# PCB_3U_RJ45.net
KiCad netlist of a schematic drawn in Altium Designer
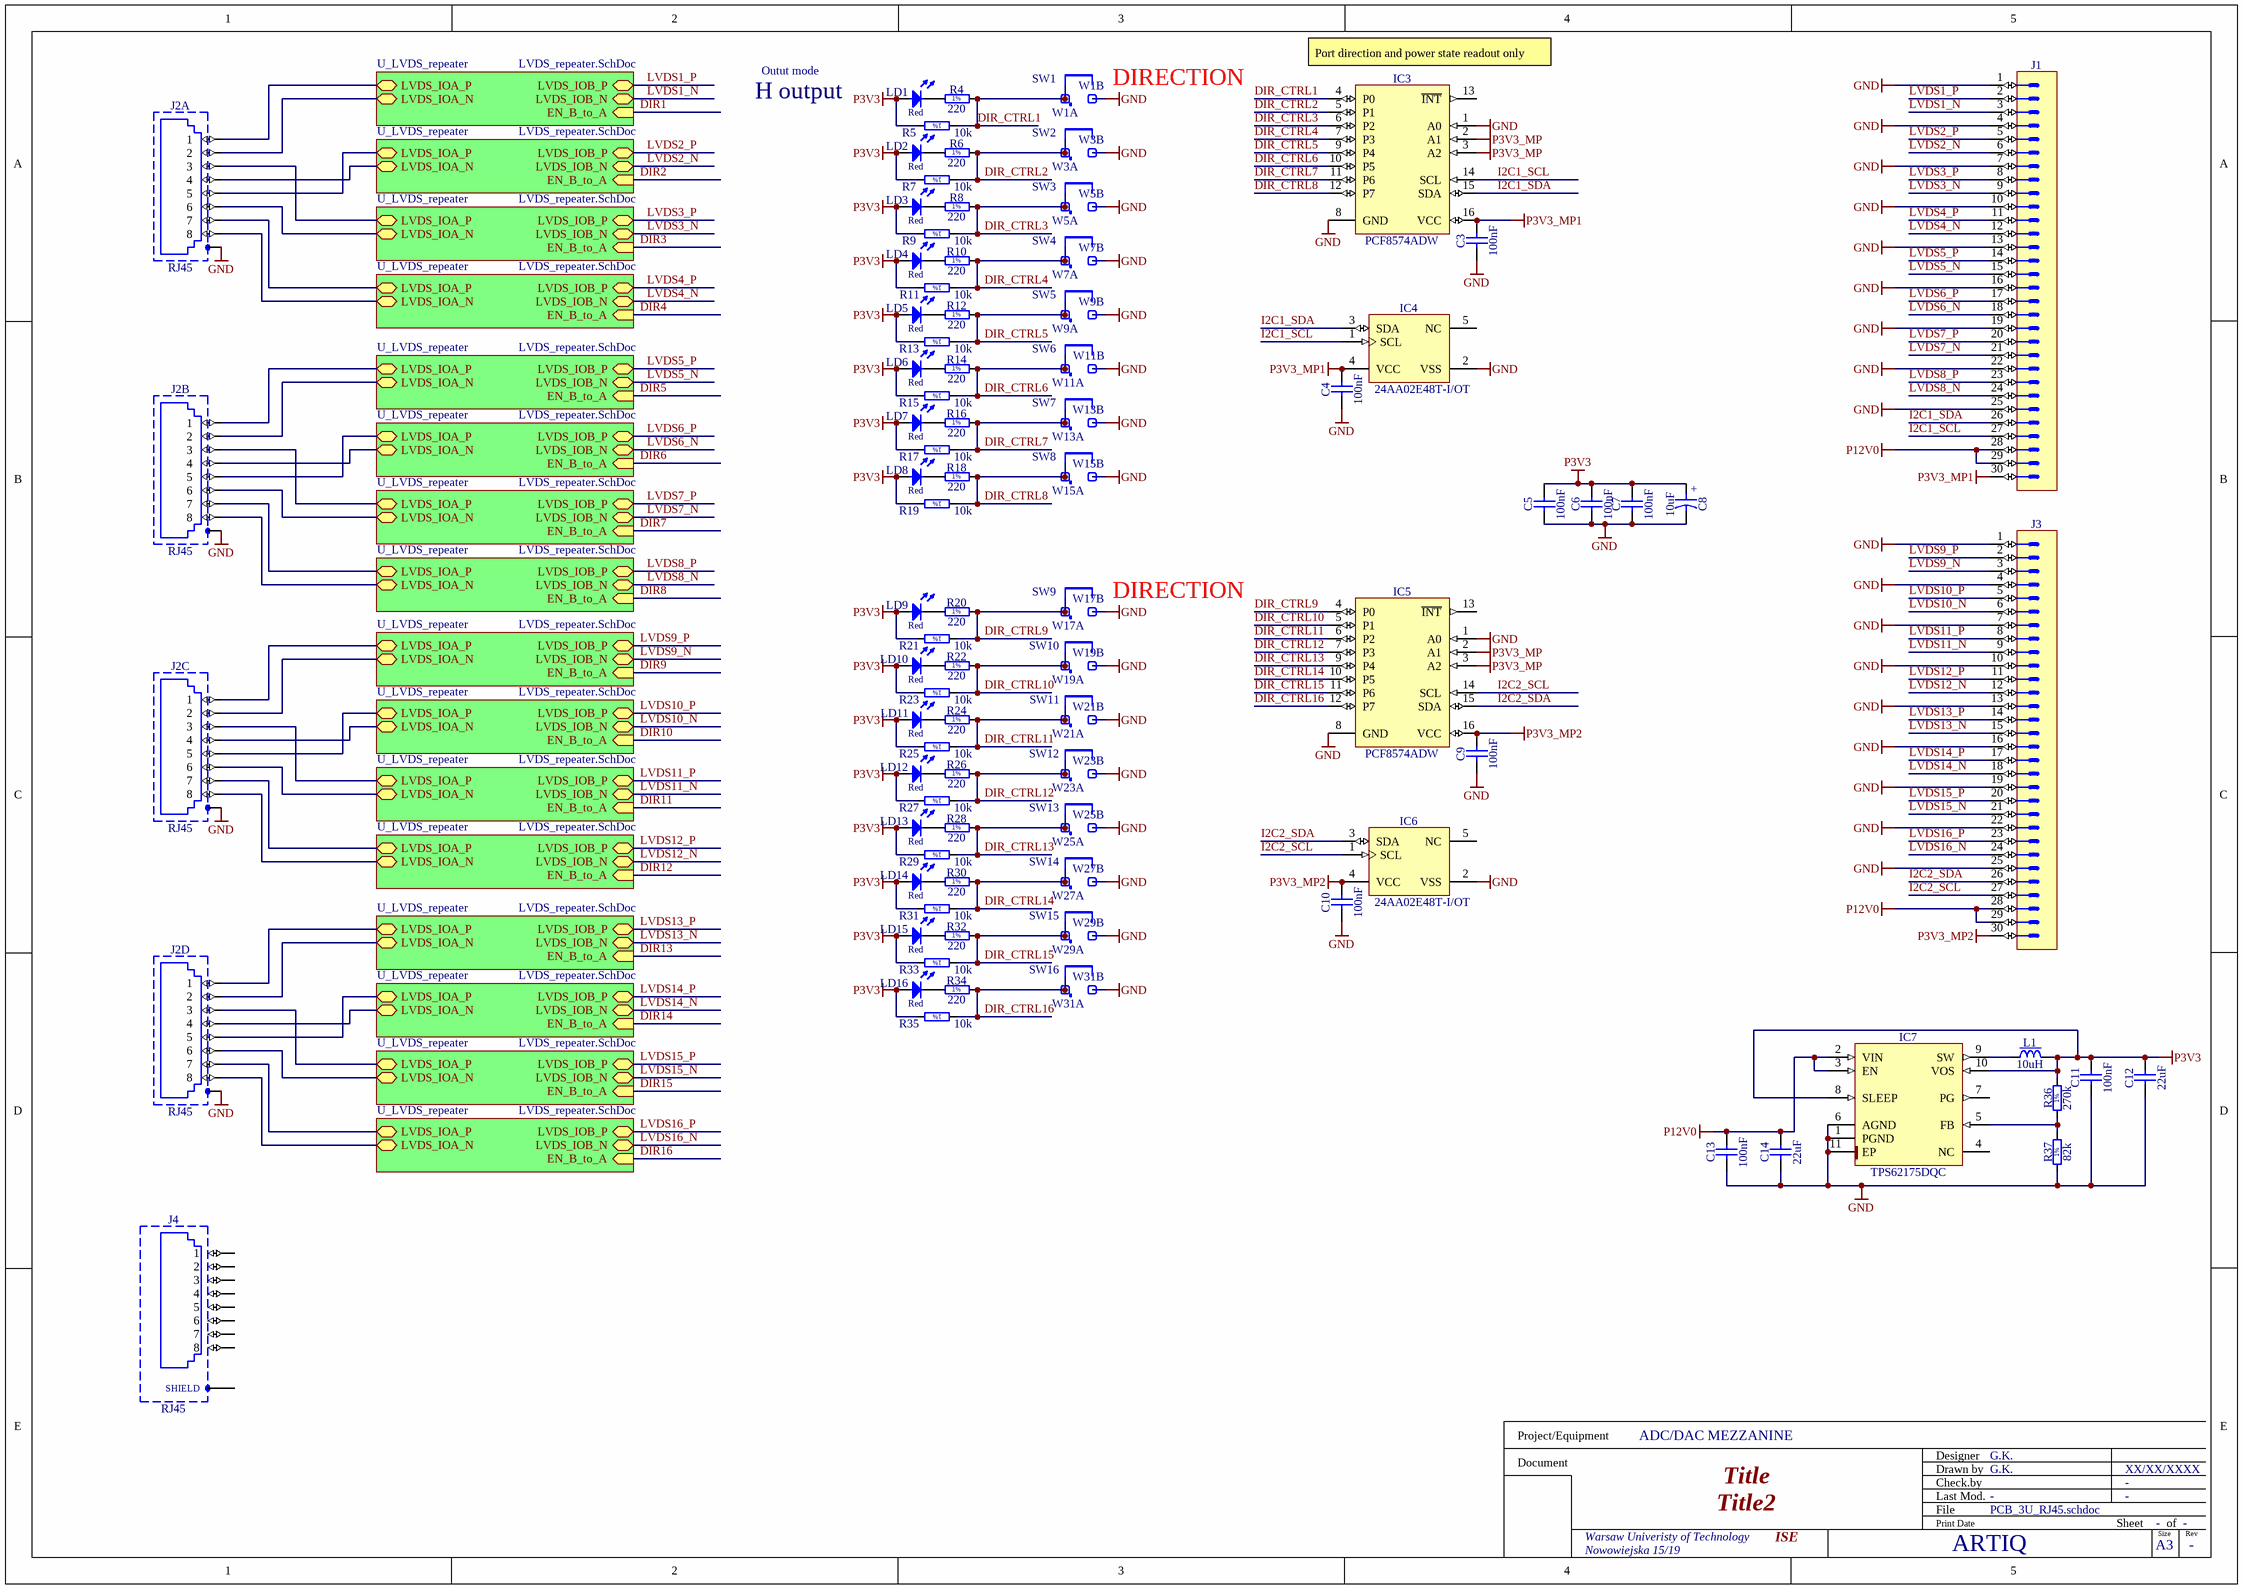
[diagram p0: PCB_3U_RJ45.schdoc]

(export (version "E")
  (design (tool "Eeschema 10.0.6"))
  (components
    (comp (ref "C3")
      (value "100nF")
      (footprint "CAPC1005X55N")
      (description "Non-polarised capacitor")
      (fields
        (field (name "PART NUMBER") "CC0402_100NF_16V_10%_X5R")
        (field (name "VOLTAGE") "16V")
        (field (name "AUTHOR") "CERN DEM JLC")
      )
      (libsource (lib "Capacitors") (part "Capacitor - non polarized"))
    )
    (comp (ref "C4")
      (value "100nF")
      (footprint "CAPC1005X55N")
      (description "Non-polarised capacitor")
      (fields
        (field (name "PART NUMBER") "CC0402_100NF_16V_10%_X5R")
        (field (name "VOLTAGE") "16V")
        (field (name "AUTHOR") "CERN DEM JLC")
      )
      (libsource (lib "Capacitors") (part "Capacitor - non polarized"))
    )
    (comp (ref "C5")
      (value "100nF")
      (footprint "CAPC1005X55N")
      (description "Non-polarised capacitor")
      (fields
        (field (name "PART NUMBER") "CC0402_100NF_16V_10%_X5R")
        (field (name "VOLTAGE") "16V")
        (field (name "AUTHOR") "CERN DEM JLC")
      )
      (libsource (lib "Capacitors") (part "Capacitor - non polarized"))
    )
    (comp (ref "C6")
      (value "100nF")
      (footprint "CAPC1005X55N")
      (description "Non-polarised capacitor")
      (fields
        (field (name "PART NUMBER") "CC0402_100NF_16V_10%_X5R")
        (field (name "VOLTAGE") "16V")
        (field (name "AUTHOR") "CERN DEM JLC")
      )
      (libsource (lib "Capacitors") (part "Capacitor - non polarized"))
    )
    (comp (ref "C7")
      (value "100nF")
      (footprint "CAPC1005X55N")
      (description "Non-polarised capacitor")
      (fields
        (field (name "PART NUMBER") "CC0402_100NF_16V_10%_X5R")
        (field (name "VOLTAGE") "16V")
        (field (name "AUTHOR") "CERN DEM JLC")
      )
      (libsource (lib "Capacitors") (part "Capacitor - non polarized"))
    )
    (comp (ref "C8")
      (value "10uF")
      (footprint "CAPAE430X540N")
      (description "Polarised capacitor")
      (fields
        (field (name "PART NUMBER") "CAE430-540_10UF_16V_20%")
        (field (name "VOLTAGE") "16V")
        (field (name "AUTHOR") "CERN DEM JLC")
      )
      (libsource (lib "Capacitors") (part "Capacitor - polarized"))
    )
    (comp (ref "C9")
      (value "100nF")
      (footprint "CAPC1005X55N")
      (description "Non-polarised capacitor")
      (fields
        (field (name "PART NUMBER") "CC0402_100NF_16V_10%_X5R")
        (field (name "VOLTAGE") "16V")
        (field (name "AUTHOR") "CERN DEM JLC")
      )
      (libsource (lib "Capacitors") (part "Capacitor - non polarized"))
    )
    (comp (ref "C10")
      (value "100nF")
      (footprint "CAPC1005X55N")
      (description "Non-polarised capacitor")
      (fields
        (field (name "PART NUMBER") "CC0402_100NF_16V_10%_X5R")
        (field (name "VOLTAGE") "16V")
        (field (name "AUTHOR") "CERN DEM JLC")
      )
      (libsource (lib "Capacitors") (part "Capacitor - non polarized"))
    )
    (comp (ref "C11")
      (value "100nF")
      (footprint "CAPC1005X55N")
      (description "Non-polarised capacitor")
      (fields
        (field (name "PART NUMBER") "CC0402_100NF_16V_10%_X5R")
        (field (name "VOLTAGE") "16V")
        (field (name "AUTHOR") "CERN DEM JLC")
      )
      (libsource (lib "Capacitors") (part "Capacitor - non polarized"))
    )
    (comp (ref "C12")
      (value "22uF")
      (footprint "CAPC2012X135N")
      (description "Non-polarised capacitor")
      (fields
        (field (name "PART NUMBER") "CC0805_22UF_16V_10%_X5R")
        (field (name "VOLTAGE") "16V")
        (field (name "AUTHOR") "CERN DEM JLC")
      )
      (libsource (lib "Capacitors") (part "Capacitor - non polarized"))
    )
    (comp (ref "C13")
      (value "100nF")
      (footprint "CAPC1005X55N")
      (description "Non-polarised capacitor")
      (fields
        (field (name "PART NUMBER") "CC0402_100NF_16V_10%_X5R")
        (field (name "VOLTAGE") "16V")
        (field (name "AUTHOR") "CERN DEM JLC")
      )
      (libsource (lib "Capacitors") (part "Capacitor - non polarized"))
    )
    (comp (ref "C14")
      (value "22uF")
      (footprint "CAPC2012X135N")
      (description "Non-polarised capacitor")
      (fields
        (field (name "PART NUMBER") "CC0805_22UF_16V_10%_X5R")
        (field (name "VOLTAGE") "16V")
        (field (name "AUTHOR") "CERN DEM JLC")
      )
      (libsource (lib "Capacitors") (part "Capacitor - non polarized"))
    )
    (comp (ref "IC3")
      (value "PCF8574ADW")
      (footprint "SOIC127P1030X265-16N")
      (description "Remote 8-bit I/O Expander For I2C Bus")
      (fields (field (name "MANUFACTURER") "TEXAS INSTRUMENTS") (field (name "AUTHOR") "CERN DEM JLC"))
      (libsource (lib "ICs And Semiconductors") (part "PCF8574ADW"))
    )
    (comp (ref "IC4")
      (value "24AA02E48T-I/OT")
      (footprint "SOT95P280X145-5N")
      (description "1.7V-5.5V, 2K I2C Serial EEPROM With EUI-48 Node Identity")
      (fields (field (name "MANUFACTURER") "MICROCHIP TECHNOLOGY") (field (name "AUTHOR") "CERN DEM MR"))
      (libsource (lib "ICs And Semiconductors") (part "24AA02E48T-I/OT"))
    )
    (comp (ref "IC5")
      (value "PCF8574ADW")
      (footprint "SOIC127P1030X265-16N")
      (description "Remote 8-bit I/O Expander For I2C Bus")
      (fields (field (name "MANUFACTURER") "TEXAS INSTRUMENTS") (field (name "AUTHOR") "CERN DEM JLC"))
      (libsource (lib "ICs And Semiconductors") (part "PCF8574ADW"))
    )
    (comp (ref "IC6")
      (value "24AA02E48T-I/OT")
      (footprint "SOT95P280X145-5N")
      (description "1.7V-5.5V, 2K I2C Serial EEPROM With EUI-48 Node Identity")
      (fields (field (name "MANUFACTURER") "MICROCHIP TECHNOLOGY") (field (name "AUTHOR") "CERN DEM MR"))
      (libsource (lib "ICs And Semiconductors") (part "24AA02E48T-I/OT"))
    )
    (comp (ref "IC7")
      (value "TPS62175DQC")
      (footprint "SON50P200X300X80-11N-R94X250")
      (description "4.75-28VDC to 1-6VDC, 500mA Step-Down Converter With Sleep Mode")
      (fields (field (name "MANUFACTURER") "TEXAS INSTRUMENTS") (field (name "AUTHOR") "CERN DEM JMW"))
      (libsource (lib "ICs And Semiconductors") (part "TPS62175"))
    )
    (comp (ref "J1")
      (value "~")
      (footprint "3M_N2530-6002RB")
      (description "Connector 30 Male")
      (fields
        (field (name "PART NUMBER") "3M_N2530-6002RB")
        (field (name "MANUFACTURER") "3M")
        (field (name "AUTHOR") "CERN DEM JLC")
      )
      (libsource (lib "Connectors") (part "Connector 30 Male"))
    )
    (comp (ref "J2")
      (value "RJ45")
      (footprint "TYCO_5406203-3")
      (description "Connector 4 x RJ45 + Shield")
      (fields
        (field (name "PART NUMBER") "TYCO_5406203-3")
        (field (name "MANUFACTURER") "TYCO ELECTRONICS")
        (field (name "AUTHOR") "CERN DEM JLC")
      )
      (libsource (lib "Connectors") (part "Connector 4 x RJ45 + Shield"))
    )
    (comp (ref "J3")
      (value "~")
      (footprint "3M_N2530-6002RB")
      (description "Connector 30 Male")
      (fields
        (field (name "PART NUMBER") "3M_N2530-6002RB")
        (field (name "MANUFACTURER") "3M")
        (field (name "AUTHOR") "CERN DEM JLC")
      )
      (libsource (lib "Connectors") (part "Connector 30 Male"))
    )
    (comp (ref "J4")
      (value "RJ45")
      (footprint "FCI_95678-001LF")
      (description "1 Port, 8 Positions Shielded Snap PEG, CAT5 RJ45 Horizontal Modular Jack")
      (fields
        (field (name "PART NUMBER") "FCI_95678-001LF")
        (field (name "MANUFACTURER") "FCI")
        (field (name "AUTHOR") "CERN DEM BC")
      )
      (libsource (lib "Connectors") (part "FCI_95678-001LF"))
    )
    (comp (ref "L1")
      (value "10uH")
      (footprint "IND_MURATA-PS_8400")
      (description "Inductor With Core")
      (fields
        (field (name "PART NUMBER") "IND_10UH_10%_MURATA-PS_8400")
        (field (name "POWER") "950mA")
        (field (name "AUTHOR") "CERN DEM JLC")
      )
      (libsource (lib "Inductors & Transformers") (part "Inductor With Magnetic core"))
    )
    (comp (ref "LD1")
      (value "Red")
      (footprint "LED_AVAGO_HSMC-C120")
      (description "LED Red 1C 2A")
      (fields
        (field (name "PART NUMBER") "LED_AVAGO_HSMC-C120")
        (field (name "MANUFACTURER") "AVAGO TECHNOLOGIES")
        (field (name "AUTHOR") "CERN DEM JMW")
      )
      (libsource (lib "ICs And Semiconductors") (part "LED Red 1C 2A"))
    )
    (comp (ref "LD2")
      (value "Red")
      (footprint "LED_AVAGO_HSMC-C120")
      (description "LED Red 1C 2A")
      (fields
        (field (name "PART NUMBER") "LED_AVAGO_HSMC-C120")
        (field (name "MANUFACTURER") "AVAGO TECHNOLOGIES")
        (field (name "AUTHOR") "CERN DEM JMW")
      )
      (libsource (lib "ICs And Semiconductors") (part "LED Red 1C 2A"))
    )
    (comp (ref "LD3")
      (value "Red")
      (footprint "LED_AVAGO_HSMC-C120")
      (description "LED Red 1C 2A")
      (fields
        (field (name "PART NUMBER") "LED_AVAGO_HSMC-C120")
        (field (name "MANUFACTURER") "AVAGO TECHNOLOGIES")
        (field (name "AUTHOR") "CERN DEM JMW")
      )
      (libsource (lib "ICs And Semiconductors") (part "LED Red 1C 2A"))
    )
    (comp (ref "LD4")
      (value "Red")
      (footprint "LED_AVAGO_HSMC-C120")
      (description "LED Red 1C 2A")
      (fields
        (field (name "PART NUMBER") "LED_AVAGO_HSMC-C120")
        (field (name "MANUFACTURER") "AVAGO TECHNOLOGIES")
        (field (name "AUTHOR") "CERN DEM JMW")
      )
      (libsource (lib "ICs And Semiconductors") (part "LED Red 1C 2A"))
    )
    (comp (ref "LD5")
      (value "Red")
      (footprint "LED_AVAGO_HSMC-C120")
      (description "LED Red 1C 2A")
      (fields
        (field (name "PART NUMBER") "LED_AVAGO_HSMC-C120")
        (field (name "MANUFACTURER") "AVAGO TECHNOLOGIES")
        (field (name "AUTHOR") "CERN DEM JMW")
      )
      (libsource (lib "ICs And Semiconductors") (part "LED Red 1C 2A"))
    )
    (comp (ref "LD6")
      (value "Red")
      (footprint "LED_AVAGO_HSMC-C120")
      (description "LED Red 1C 2A")
      (fields
        (field (name "PART NUMBER") "LED_AVAGO_HSMC-C120")
        (field (name "MANUFACTURER") "AVAGO TECHNOLOGIES")
        (field (name "AUTHOR") "CERN DEM JMW")
      )
      (libsource (lib "ICs And Semiconductors") (part "LED Red 1C 2A"))
    )
    (comp (ref "LD7")
      (value "Red")
      (footprint "LED_AVAGO_HSMC-C120")
      (description "LED Red 1C 2A")
      (fields
        (field (name "PART NUMBER") "LED_AVAGO_HSMC-C120")
        (field (name "MANUFACTURER") "AVAGO TECHNOLOGIES")
        (field (name "AUTHOR") "CERN DEM JMW")
      )
      (libsource (lib "ICs And Semiconductors") (part "LED Red 1C 2A"))
    )
    (comp (ref "LD8")
      (value "Red")
      (footprint "LED_AVAGO_HSMC-C120")
      (description "LED Red 1C 2A")
      (fields
        (field (name "PART NUMBER") "LED_AVAGO_HSMC-C120")
        (field (name "MANUFACTURER") "AVAGO TECHNOLOGIES")
        (field (name "AUTHOR") "CERN DEM JMW")
      )
      (libsource (lib "ICs And Semiconductors") (part "LED Red 1C 2A"))
    )
    (comp (ref "LD9")
      (value "Red")
      (footprint "LED_AVAGO_HSMC-C120")
      (description "LED Red 1C 2A")
      (fields
        (field (name "PART NUMBER") "LED_AVAGO_HSMC-C120")
        (field (name "MANUFACTURER") "AVAGO TECHNOLOGIES")
        (field (name "AUTHOR") "CERN DEM JMW")
      )
      (libsource (lib "ICs And Semiconductors") (part "LED Red 1C 2A"))
    )
    (comp (ref "LD10")
      (value "Red")
      (footprint "LED_AVAGO_HSMC-C120")
      (description "LED Red 1C 2A")
      (fields
        (field (name "PART NUMBER") "LED_AVAGO_HSMC-C120")
        (field (name "MANUFACTURER") "AVAGO TECHNOLOGIES")
        (field (name "AUTHOR") "CERN DEM JMW")
      )
      (libsource (lib "ICs And Semiconductors") (part "LED Red 1C 2A"))
    )
    (comp (ref "LD11")
      (value "Red")
      (footprint "LED_AVAGO_HSMC-C120")
      (description "LED Red 1C 2A")
      (fields
        (field (name "PART NUMBER") "LED_AVAGO_HSMC-C120")
        (field (name "MANUFACTURER") "AVAGO TECHNOLOGIES")
        (field (name "AUTHOR") "CERN DEM JMW")
      )
      (libsource (lib "ICs And Semiconductors") (part "LED Red 1C 2A"))
    )
    (comp (ref "LD12")
      (value "Red")
      (footprint "LED_AVAGO_HSMC-C120")
      (description "LED Red 1C 2A")
      (fields
        (field (name "PART NUMBER") "LED_AVAGO_HSMC-C120")
        (field (name "MANUFACTURER") "AVAGO TECHNOLOGIES")
        (field (name "AUTHOR") "CERN DEM JMW")
      )
      (libsource (lib "ICs And Semiconductors") (part "LED Red 1C 2A"))
    )
    (comp (ref "LD13")
      (value "Red")
      (footprint "LED_AVAGO_HSMC-C120")
      (description "LED Red 1C 2A")
      (fields
        (field (name "PART NUMBER") "LED_AVAGO_HSMC-C120")
        (field (name "MANUFACTURER") "AVAGO TECHNOLOGIES")
        (field (name "AUTHOR") "CERN DEM JMW")
      )
      (libsource (lib "ICs And Semiconductors") (part "LED Red 1C 2A"))
    )
    (comp (ref "LD14")
      (value "Red")
      (footprint "LED_AVAGO_HSMC-C120")
      (description "LED Red 1C 2A")
      (fields
        (field (name "PART NUMBER") "LED_AVAGO_HSMC-C120")
        (field (name "MANUFACTURER") "AVAGO TECHNOLOGIES")
        (field (name "AUTHOR") "CERN DEM JMW")
      )
      (libsource (lib "ICs And Semiconductors") (part "LED Red 1C 2A"))
    )
    (comp (ref "LD15")
      (value "Red")
      (footprint "LED_AVAGO_HSMC-C120")
      (description "LED Red 1C 2A")
      (fields
        (field (name "PART NUMBER") "LED_AVAGO_HSMC-C120")
        (field (name "MANUFACTURER") "AVAGO TECHNOLOGIES")
        (field (name "AUTHOR") "CERN DEM JMW")
      )
      (libsource (lib "ICs And Semiconductors") (part "LED Red 1C 2A"))
    )
    (comp (ref "LD16")
      (value "Red")
      (footprint "LED_AVAGO_HSMC-C120")
      (description "LED Red 1C 2A")
      (fields
        (field (name "PART NUMBER") "LED_AVAGO_HSMC-C120")
        (field (name "MANUFACTURER") "AVAGO TECHNOLOGIES")
        (field (name "AUTHOR") "CERN DEM JMW")
      )
      (libsource (lib "ICs And Semiconductors") (part "LED Red 1C 2A"))
    )
    (comp (ref "R4")
      (value "220")
      (footprint "RESC1608X55N")
      (description "Resistor - 1%")
      (fields
        (field (name "PART NUMBER") "R0603_220R_1%_0.1W_100PPM")
        (field (name "POWER") "0.1W")
        (field (name "AUTHOR") "CERN DEM JLC")
      )
      (libsource (lib "Resistors") (part "Resistor - 1%"))
    )
    (comp (ref "R5")
      (value "10k")
      (footprint "RESC1005X40N")
      (description "Resistor - 1%")
      (fields
        (field (name "PART NUMBER") "R0402_10K_1%_0.0625W_100PPM")
        (field (name "POWER") "0.0625W")
        (field (name "AUTHOR") "CERN DEM JLC")
      )
      (libsource (lib "Resistors") (part "Resistor - 1%"))
    )
    (comp (ref "R6")
      (value "220")
      (footprint "RESC1608X55N")
      (description "Resistor - 1%")
      (fields
        (field (name "PART NUMBER") "R0603_220R_1%_0.1W_100PPM")
        (field (name "POWER") "0.1W")
        (field (name "AUTHOR") "CERN DEM JLC")
      )
      (libsource (lib "Resistors") (part "Resistor - 1%"))
    )
    (comp (ref "R7")
      (value "10k")
      (footprint "RESC1005X40N")
      (description "Resistor - 1%")
      (fields
        (field (name "PART NUMBER") "R0402_10K_1%_0.0625W_100PPM")
        (field (name "POWER") "0.0625W")
        (field (name "AUTHOR") "CERN DEM JLC")
      )
      (libsource (lib "Resistors") (part "Resistor - 1%"))
    )
    (comp (ref "R8")
      (value "220")
      (footprint "RESC1608X55N")
      (description "Resistor - 1%")
      (fields
        (field (name "PART NUMBER") "R0603_220R_1%_0.1W_100PPM")
        (field (name "POWER") "0.1W")
        (field (name "AUTHOR") "CERN DEM JLC")
      )
      (libsource (lib "Resistors") (part "Resistor - 1%"))
    )
    (comp (ref "R9")
      (value "10k")
      (footprint "RESC1005X40N")
      (description "Resistor - 1%")
      (fields
        (field (name "PART NUMBER") "R0402_10K_1%_0.0625W_100PPM")
        (field (name "POWER") "0.0625W")
        (field (name "AUTHOR") "CERN DEM JLC")
      )
      (libsource (lib "Resistors") (part "Resistor - 1%"))
    )
    (comp (ref "R10")
      (value "220")
      (footprint "RESC1608X55N")
      (description "Resistor - 1%")
      (fields
        (field (name "PART NUMBER") "R0603_220R_1%_0.1W_100PPM")
        (field (name "POWER") "0.1W")
        (field (name "AUTHOR") "CERN DEM JLC")
      )
      (libsource (lib "Resistors") (part "Resistor - 1%"))
    )
    (comp (ref "R11")
      (value "10k")
      (footprint "RESC1005X40N")
      (description "Resistor - 1%")
      (fields
        (field (name "PART NUMBER") "R0402_10K_1%_0.0625W_100PPM")
        (field (name "POWER") "0.0625W")
        (field (name "AUTHOR") "CERN DEM JLC")
      )
      (libsource (lib "Resistors") (part "Resistor - 1%"))
    )
    (comp (ref "R12")
      (value "220")
      (footprint "RESC1608X55N")
      (description "Resistor - 1%")
      (fields
        (field (name "PART NUMBER") "R0603_220R_1%_0.1W_100PPM")
        (field (name "POWER") "0.1W")
        (field (name "AUTHOR") "CERN DEM JLC")
      )
      (libsource (lib "Resistors") (part "Resistor - 1%"))
    )
    (comp (ref "R13")
      (value "10k")
      (footprint "RESC1005X40N")
      (description "Resistor - 1%")
      (fields
        (field (name "PART NUMBER") "R0402_10K_1%_0.0625W_100PPM")
        (field (name "POWER") "0.0625W")
        (field (name "AUTHOR") "CERN DEM JLC")
      )
      (libsource (lib "Resistors") (part "Resistor - 1%"))
    )
    (comp (ref "R14")
      (value "220")
      (footprint "RESC1608X55N")
      (description "Resistor - 1%")
      (fields
        (field (name "PART NUMBER") "R0603_220R_1%_0.1W_100PPM")
        (field (name "POWER") "0.1W")
        (field (name "AUTHOR") "CERN DEM JLC")
      )
      (libsource (lib "Resistors") (part "Resistor - 1%"))
    )
    (comp (ref "R15")
      (value "10k")
      (footprint "RESC1005X40N")
      (description "Resistor - 1%")
      (fields
        (field (name "PART NUMBER") "R0402_10K_1%_0.0625W_100PPM")
        (field (name "POWER") "0.0625W")
        (field (name "AUTHOR") "CERN DEM JLC")
      )
      (libsource (lib "Resistors") (part "Resistor - 1%"))
    )
    (comp (ref "R16")
      (value "220")
      (footprint "RESC1608X55N")
      (description "Resistor - 1%")
      (fields
        (field (name "PART NUMBER") "R0603_220R_1%_0.1W_100PPM")
        (field (name "POWER") "0.1W")
        (field (name "AUTHOR") "CERN DEM JLC")
      )
      (libsource (lib "Resistors") (part "Resistor - 1%"))
    )
    (comp (ref "R17")
      (value "10k")
      (footprint "RESC1005X40N")
      (description "Resistor - 1%")
      (fields
        (field (name "PART NUMBER") "R0402_10K_1%_0.0625W_100PPM")
        (field (name "POWER") "0.0625W")
        (field (name "AUTHOR") "CERN DEM JLC")
      )
      (libsource (lib "Resistors") (part "Resistor - 1%"))
    )
    (comp (ref "R18")
      (value "220")
      (footprint "RESC1608X55N")
      (description "Resistor - 1%")
      (fields
        (field (name "PART NUMBER") "R0603_220R_1%_0.1W_100PPM")
        (field (name "POWER") "0.1W")
        (field (name "AUTHOR") "CERN DEM JLC")
      )
      (libsource (lib "Resistors") (part "Resistor - 1%"))
    )
    (comp (ref "R19")
      (value "10k")
      (footprint "RESC1005X40N")
      (description "Resistor - 1%")
      (fields
        (field (name "PART NUMBER") "R0402_10K_1%_0.0625W_100PPM")
        (field (name "POWER") "0.0625W")
        (field (name "AUTHOR") "CERN DEM JLC")
      )
      (libsource (lib "Resistors") (part "Resistor - 1%"))
    )
    (comp (ref "R20")
      (value "220")
      (footprint "RESC1608X55N")
      (description "Resistor - 1%")
      (fields
        (field (name "PART NUMBER") "R0603_220R_1%_0.1W_100PPM")
        (field (name "POWER") "0.1W")
        (field (name "AUTHOR") "CERN DEM JLC")
      )
      (libsource (lib "Resistors") (part "Resistor - 1%"))
    )
    (comp (ref "R21")
      (value "10k")
      (footprint "RESC1005X40N")
      (description "Resistor - 1%")
      (fields
        (field (name "PART NUMBER") "R0402_10K_1%_0.0625W_100PPM")
        (field (name "POWER") "0.0625W")
        (field (name "AUTHOR") "CERN DEM JLC")
      )
      (libsource (lib "Resistors") (part "Resistor - 1%"))
    )
    (comp (ref "R22")
      (value "220")
      (footprint "RESC1608X55N")
      (description "Resistor - 1%")
      (fields
        (field (name "PART NUMBER") "R0603_220R_1%_0.1W_100PPM")
        (field (name "POWER") "0.1W")
        (field (name "AUTHOR") "CERN DEM JLC")
      )
      (libsource (lib "Resistors") (part "Resistor - 1%"))
    )
    (comp (ref "R23")
      (value "10k")
      (footprint "RESC1005X40N")
      (description "Resistor - 1%")
      (fields
        (field (name "PART NUMBER") "R0402_10K_1%_0.0625W_100PPM")
        (field (name "POWER") "0.0625W")
        (field (name "AUTHOR") "CERN DEM JLC")
      )
      (libsource (lib "Resistors") (part "Resistor - 1%"))
    )
    (comp (ref "R24")
      (value "220")
      (footprint "RESC1608X55N")
      (description "Resistor - 1%")
      (fields
        (field (name "PART NUMBER") "R0603_220R_1%_0.1W_100PPM")
        (field (name "POWER") "0.1W")
        (field (name "AUTHOR") "CERN DEM JLC")
      )
      (libsource (lib "Resistors") (part "Resistor - 1%"))
    )
    (comp (ref "R25")
      (value "10k")
      (footprint "RESC1005X40N")
      (description "Resistor - 1%")
      (fields
        (field (name "PART NUMBER") "R0402_10K_1%_0.0625W_100PPM")
        (field (name "POWER") "0.0625W")
        (field (name "AUTHOR") "CERN DEM JLC")
      )
      (libsource (lib "Resistors") (part "Resistor - 1%"))
    )
    (comp (ref "R26")
      (value "220")
      (footprint "RESC1608X55N")
      (description "Resistor - 1%")
      (fields
        (field (name "PART NUMBER") "R0603_220R_1%_0.1W_100PPM")
        (field (name "POWER") "0.1W")
        (field (name "AUTHOR") "CERN DEM JLC")
      )
      (libsource (lib "Resistors") (part "Resistor - 1%"))
    )
    (comp (ref "R27")
      (value "10k")
      (footprint "RESC1005X40N")
      (description "Resistor - 1%")
      (fields
        (field (name "PART NUMBER") "R0402_10K_1%_0.0625W_100PPM")
        (field (name "POWER") "0.0625W")
        (field (name "AUTHOR") "CERN DEM JLC")
      )
      (libsource (lib "Resistors") (part "Resistor - 1%"))
    )
    (comp (ref "R28")
      (value "220")
      (footprint "RESC1608X55N")
      (description "Resistor - 1%")
      (fields
        (field (name "PART NUMBER") "R0603_220R_1%_0.1W_100PPM")
        (field (name "POWER") "0.1W")
        (field (name "AUTHOR") "CERN DEM JLC")
      )
      (libsource (lib "Resistors") (part "Resistor - 1%"))
    )
    (comp (ref "R29")
      (value "10k")
      (footprint "RESC1005X40N")
      (description "Resistor - 1%")
      (fields
        (field (name "PART NUMBER") "R0402_10K_1%_0.0625W_100PPM")
        (field (name "POWER") "0.0625W")
        (field (name "AUTHOR") "CERN DEM JLC")
      )
      (libsource (lib "Resistors") (part "Resistor - 1%"))
    )
    (comp (ref "R30")
      (value "220")
      (footprint "RESC1608X55N")
      (description "Resistor - 1%")
      (fields
        (field (name "PART NUMBER") "R0603_220R_1%_0.1W_100PPM")
        (field (name "POWER") "0.1W")
        (field (name "AUTHOR") "CERN DEM JLC")
      )
      (libsource (lib "Resistors") (part "Resistor - 1%"))
    )
    (comp (ref "R31")
      (value "10k")
      (footprint "RESC1005X40N")
      (description "Resistor - 1%")
      (fields
        (field (name "PART NUMBER") "R0402_10K_1%_0.0625W_100PPM")
        (field (name "POWER") "0.0625W")
        (field (name "AUTHOR") "CERN DEM JLC")
      )
      (libsource (lib "Resistors") (part "Resistor - 1%"))
    )
    (comp (ref "R32")
      (value "220")
      (footprint "RESC1608X55N")
      (description "Resistor - 1%")
      (fields
        (field (name "PART NUMBER") "R0603_220R_1%_0.1W_100PPM")
        (field (name "POWER") "0.1W")
        (field (name "AUTHOR") "CERN DEM JLC")
      )
      (libsource (lib "Resistors") (part "Resistor - 1%"))
    )
    (comp (ref "R33")
      (value "10k")
      (footprint "RESC1005X40N")
      (description "Resistor - 1%")
      (fields
        (field (name "PART NUMBER") "R0402_10K_1%_0.0625W_100PPM")
        (field (name "POWER") "0.0625W")
        (field (name "AUTHOR") "CERN DEM JLC")
      )
      (libsource (lib "Resistors") (part "Resistor - 1%"))
    )
    (comp (ref "R34")
      (value "220")
      (footprint "RESC1608X55N")
      (description "Resistor - 1%")
      (fields
        (field (name "PART NUMBER") "R0603_220R_1%_0.1W_100PPM")
        (field (name "POWER") "0.1W")
        (field (name "AUTHOR") "CERN DEM JLC")
      )
      (libsource (lib "Resistors") (part "Resistor - 1%"))
    )
    (comp (ref "R35")
      (value "10k")
      (footprint "RESC1005X40N")
      (description "Resistor - 1%")
      (fields
        (field (name "PART NUMBER") "R0402_10K_1%_0.0625W_100PPM")
        (field (name "POWER") "0.0625W")
        (field (name "AUTHOR") "CERN DEM JLC")
      )
      (libsource (lib "Resistors") (part "Resistor - 1%"))
    )
    (comp (ref "R36")
      (value "270k")
      (footprint "RESC1608X55N")
      (description "Resistor - 1%")
      (fields
        (field (name "PART NUMBER") "R0603_270K_1%_0.1W_100PPM")
        (field (name "POWER") "0.1W")
        (field (name "AUTHOR") "CERN DEM JLC")
      )
      (libsource (lib "Resistors") (part "Resistor - 1%"))
    )
    (comp (ref "R37")
      (value "82k")
      (footprint "RESC1608X55N")
      (description "Resistor - 1%")
      (fields
        (field (name "PART NUMBER") "R0603_82K_1%_0.1W_100PPM")
        (field (name "POWER") "0.1W")
        (field (name "AUTHOR") "CERN DEM JLC")
      )
      (libsource (lib "Resistors") (part "Resistor - 1%"))
    )
    (comp (ref "SW1")
      (value "Jumper Type1")
      (footprint "JUMPER_BLACK_INSULATED_2.54MM")
      (description "Jumper 1 Pin")
      (fields
        (field (name "PART NUMBER") "COMATEL_313.1730.0.00.40.0")
        (field (name "MANUFACTURER") "KONTEK COMATEL")
        (field (name "AUTHOR") "CERN DEM JLC")
      )
      (libsource (lib "Connectors") (part "Jumper Type1"))
    )
    (comp (ref "SW2")
      (value "Jumper Type1")
      (footprint "JUMPER_BLACK_INSULATED_2.54MM")
      (description "Jumper 1 Pin")
      (fields
        (field (name "PART NUMBER") "COMATEL_313.1730.0.00.40.0")
        (field (name "MANUFACTURER") "KONTEK COMATEL")
        (field (name "AUTHOR") "CERN DEM JLC")
      )
      (libsource (lib "Connectors") (part "Jumper Type1"))
    )
    (comp (ref "SW3")
      (value "Jumper Type1")
      (footprint "JUMPER_BLACK_INSULATED_2.54MM")
      (description "Jumper 1 Pin")
      (fields
        (field (name "PART NUMBER") "COMATEL_313.1730.0.00.40.0")
        (field (name "MANUFACTURER") "KONTEK COMATEL")
        (field (name "AUTHOR") "CERN DEM JLC")
      )
      (libsource (lib "Connectors") (part "Jumper Type1"))
    )
    (comp (ref "SW4")
      (value "Jumper Type1")
      (footprint "JUMPER_BLACK_INSULATED_2.54MM")
      (description "Jumper 1 Pin")
      (fields
        (field (name "PART NUMBER") "COMATEL_313.1730.0.00.40.0")
        (field (name "MANUFACTURER") "KONTEK COMATEL")
        (field (name "AUTHOR") "CERN DEM JLC")
      )
      (libsource (lib "Connectors") (part "Jumper Type1"))
    )
    (comp (ref "SW5")
      (value "Jumper Type1")
      (footprint "JUMPER_BLACK_INSULATED_2.54MM")
      (description "Jumper 1 Pin")
      (fields
        (field (name "PART NUMBER") "COMATEL_313.1730.0.00.40.0")
        (field (name "MANUFACTURER") "KONTEK COMATEL")
        (field (name "AUTHOR") "CERN DEM JLC")
      )
      (libsource (lib "Connectors") (part "Jumper Type1"))
    )
    (comp (ref "SW6")
      (value "Jumper Type1")
      (footprint "JUMPER_BLACK_INSULATED_2.54MM")
      (description "Jumper 1 Pin")
      (fields
        (field (name "PART NUMBER") "COMATEL_313.1730.0.00.40.0")
        (field (name "MANUFACTURER") "KONTEK COMATEL")
        (field (name "AUTHOR") "CERN DEM JLC")
      )
      (libsource (lib "Connectors") (part "Jumper Type1"))
    )
    (comp (ref "SW7")
      (value "Jumper Type1")
      (footprint "JUMPER_BLACK_INSULATED_2.54MM")
      (description "Jumper 1 Pin")
      (fields
        (field (name "PART NUMBER") "COMATEL_313.1730.0.00.40.0")
        (field (name "MANUFACTURER") "KONTEK COMATEL")
        (field (name "AUTHOR") "CERN DEM JLC")
      )
      (libsource (lib "Connectors") (part "Jumper Type1"))
    )
    (comp (ref "SW8")
      (value "Jumper Type1")
      (footprint "JUMPER_BLACK_INSULATED_2.54MM")
      (description "Jumper 1 Pin")
      (fields
        (field (name "PART NUMBER") "COMATEL_313.1730.0.00.40.0")
        (field (name "MANUFACTURER") "KONTEK COMATEL")
        (field (name "AUTHOR") "CERN DEM JLC")
      )
      (libsource (lib "Connectors") (part "Jumper Type1"))
    )
    (comp (ref "SW9")
      (value "Jumper Type1")
      (footprint "JUMPER_BLACK_INSULATED_2.54MM")
      (description "Jumper 1 Pin")
      (fields
        (field (name "PART NUMBER") "COMATEL_313.1730.0.00.40.0")
        (field (name "MANUFACTURER") "KONTEK COMATEL")
        (field (name "AUTHOR") "CERN DEM JLC")
      )
      (libsource (lib "Connectors") (part "Jumper Type1"))
    )
    (comp (ref "SW10")
      (value "Jumper Type1")
      (footprint "JUMPER_BLACK_INSULATED_2.54MM")
      (description "Jumper 1 Pin")
      (fields
        (field (name "PART NUMBER") "COMATEL_313.1730.0.00.40.0")
        (field (name "MANUFACTURER") "KONTEK COMATEL")
        (field (name "AUTHOR") "CERN DEM JLC")
      )
      (libsource (lib "Connectors") (part "Jumper Type1"))
    )
    (comp (ref "SW11")
      (value "Jumper Type1")
      (footprint "JUMPER_BLACK_INSULATED_2.54MM")
      (description "Jumper 1 Pin")
      (fields
        (field (name "PART NUMBER") "COMATEL_313.1730.0.00.40.0")
        (field (name "MANUFACTURER") "KONTEK COMATEL")
        (field (name "AUTHOR") "CERN DEM JLC")
      )
      (libsource (lib "Connectors") (part "Jumper Type1"))
    )
    (comp (ref "SW12")
      (value "Jumper Type1")
      (footprint "JUMPER_BLACK_INSULATED_2.54MM")
      (description "Jumper 1 Pin")
      (fields
        (field (name "PART NUMBER") "COMATEL_313.1730.0.00.40.0")
        (field (name "MANUFACTURER") "KONTEK COMATEL")
        (field (name "AUTHOR") "CERN DEM JLC")
      )
      (libsource (lib "Connectors") (part "Jumper Type1"))
    )
    (comp (ref "SW13")
      (value "Jumper Type1")
      (footprint "JUMPER_BLACK_INSULATED_2.54MM")
      (description "Jumper 1 Pin")
      (fields
        (field (name "PART NUMBER") "COMATEL_313.1730.0.00.40.0")
        (field (name "MANUFACTURER") "KONTEK COMATEL")
        (field (name "AUTHOR") "CERN DEM JLC")
      )
      (libsource (lib "Connectors") (part "Jumper Type1"))
    )
    (comp (ref "SW14")
      (value "Jumper Type1")
      (footprint "JUMPER_BLACK_INSULATED_2.54MM")
      (description "Jumper 1 Pin")
      (fields
        (field (name "PART NUMBER") "COMATEL_313.1730.0.00.40.0")
        (field (name "MANUFACTURER") "KONTEK COMATEL")
        (field (name "AUTHOR") "CERN DEM JLC")
      )
      (libsource (lib "Connectors") (part "Jumper Type1"))
    )
    (comp (ref "SW15")
      (value "Jumper Type1")
      (footprint "JUMPER_BLACK_INSULATED_2.54MM")
      (description "Jumper 1 Pin")
      (fields
        (field (name "PART NUMBER") "COMATEL_313.1730.0.00.40.0")
        (field (name "MANUFACTURER") "KONTEK COMATEL")
        (field (name "AUTHOR") "CERN DEM JLC")
      )
      (libsource (lib "Connectors") (part "Jumper Type1"))
    )
    (comp (ref "SW16")
      (value "Jumper Type1")
      (footprint "JUMPER_BLACK_INSULATED_2.54MM")
      (description "Jumper 1 Pin")
      (fields
        (field (name "PART NUMBER") "COMATEL_313.1730.0.00.40.0")
        (field (name "MANUFACTURER") "KONTEK COMATEL")
        (field (name "AUTHOR") "CERN DEM JLC")
      )
      (libsource (lib "Connectors") (part "Jumper Type1"))
    )
    (comp (ref "W1")
      (value "Test Point")
      (footprint "COMATEL_385.0358.1.02.400")
      (description "2 Mini Wire-Wrap Contact Strip Header")
      (fields
        (field (name "PART NUMBER") "COMATEL_385.0358.1.02.400")
        (field (name "MANUFACTURER") "KONTEK COMATEL")
        (field (name "AUTHOR") "CERN DEM JLC")
      )
      (libsource (lib "Connectors") (part "Wire-Wrap Contact x2"))
    )
    (comp (ref "W3")
      (value "Test Point")
      (footprint "COMATEL_385.0358.1.02.400")
      (description "2 Mini Wire-Wrap Contact Strip Header")
      (fields
        (field (name "PART NUMBER") "COMATEL_385.0358.1.02.400")
        (field (name "MANUFACTURER") "KONTEK COMATEL")
        (field (name "AUTHOR") "CERN DEM JLC")
      )
      (libsource (lib "Connectors") (part "Wire-Wrap Contact x2"))
    )
    (comp (ref "W5")
      (value "Test Point")
      (footprint "COMATEL_385.0358.1.02.400")
      (description "2 Mini Wire-Wrap Contact Strip Header")
      (fields
        (field (name "PART NUMBER") "COMATEL_385.0358.1.02.400")
        (field (name "MANUFACTURER") "KONTEK COMATEL")
        (field (name "AUTHOR") "CERN DEM JLC")
      )
      (libsource (lib "Connectors") (part "Wire-Wrap Contact x2"))
    )
    (comp (ref "W7")
      (value "Test Point")
      (footprint "COMATEL_385.0358.1.02.400")
      (description "2 Mini Wire-Wrap Contact Strip Header")
      (fields
        (field (name "PART NUMBER") "COMATEL_385.0358.1.02.400")
        (field (name "MANUFACTURER") "KONTEK COMATEL")
        (field (name "AUTHOR") "CERN DEM JLC")
      )
      (libsource (lib "Connectors") (part "Wire-Wrap Contact x2"))
    )
    (comp (ref "W9")
      (value "Test Point")
      (footprint "COMATEL_385.0358.1.02.400")
      (description "2 Mini Wire-Wrap Contact Strip Header")
      (fields
        (field (name "PART NUMBER") "COMATEL_385.0358.1.02.400")
        (field (name "MANUFACTURER") "KONTEK COMATEL")
        (field (name "AUTHOR") "CERN DEM JLC")
      )
      (libsource (lib "Connectors") (part "Wire-Wrap Contact x2"))
    )
    (comp (ref "W11")
      (value "Test Point")
      (footprint "COMATEL_385.0358.1.02.400")
      (description "2 Mini Wire-Wrap Contact Strip Header")
      (fields
        (field (name "PART NUMBER") "COMATEL_385.0358.1.02.400")
        (field (name "MANUFACTURER") "KONTEK COMATEL")
        (field (name "AUTHOR") "CERN DEM JLC")
      )
      (libsource (lib "Connectors") (part "Wire-Wrap Contact x2"))
    )
    (comp (ref "W13")
      (value "Test Point")
      (footprint "COMATEL_385.0358.1.02.400")
      (description "2 Mini Wire-Wrap Contact Strip Header")
      (fields
        (field (name "PART NUMBER") "COMATEL_385.0358.1.02.400")
        (field (name "MANUFACTURER") "KONTEK COMATEL")
        (field (name "AUTHOR") "CERN DEM JLC")
      )
      (libsource (lib "Connectors") (part "Wire-Wrap Contact x2"))
    )
    (comp (ref "W15")
      (value "Test Point")
      (footprint "COMATEL_385.0358.1.02.400")
      (description "2 Mini Wire-Wrap Contact Strip Header")
      (fields
        (field (name "PART NUMBER") "COMATEL_385.0358.1.02.400")
        (field (name "MANUFACTURER") "KONTEK COMATEL")
        (field (name "AUTHOR") "CERN DEM JLC")
      )
      (libsource (lib "Connectors") (part "Wire-Wrap Contact x2"))
    )
    (comp (ref "W17")
      (value "Test Point")
      (footprint "COMATEL_385.0358.1.02.400")
      (description "2 Mini Wire-Wrap Contact Strip Header")
      (fields
        (field (name "PART NUMBER") "COMATEL_385.0358.1.02.400")
        (field (name "MANUFACTURER") "KONTEK COMATEL")
        (field (name "AUTHOR") "CERN DEM JLC")
      )
      (libsource (lib "Connectors") (part "Wire-Wrap Contact x2"))
    )
    (comp (ref "W19")
      (value "Test Point")
      (footprint "COMATEL_385.0358.1.02.400")
      (description "2 Mini Wire-Wrap Contact Strip Header")
      (fields
        (field (name "PART NUMBER") "COMATEL_385.0358.1.02.400")
        (field (name "MANUFACTURER") "KONTEK COMATEL")
        (field (name "AUTHOR") "CERN DEM JLC")
      )
      (libsource (lib "Connectors") (part "Wire-Wrap Contact x2"))
    )
    (comp (ref "W21")
      (value "Test Point")
      (footprint "COMATEL_385.0358.1.02.400")
      (description "2 Mini Wire-Wrap Contact Strip Header")
      (fields
        (field (name "PART NUMBER") "COMATEL_385.0358.1.02.400")
        (field (name "MANUFACTURER") "KONTEK COMATEL")
        (field (name "AUTHOR") "CERN DEM JLC")
      )
      (libsource (lib "Connectors") (part "Wire-Wrap Contact x2"))
    )
    (comp (ref "W23")
      (value "Test Point")
      (footprint "COMATEL_385.0358.1.02.400")
      (description "2 Mini Wire-Wrap Contact Strip Header")
      (fields
        (field (name "PART NUMBER") "COMATEL_385.0358.1.02.400")
        (field (name "MANUFACTURER") "KONTEK COMATEL")
        (field (name "AUTHOR") "CERN DEM JLC")
      )
      (libsource (lib "Connectors") (part "Wire-Wrap Contact x2"))
    )
    (comp (ref "W25")
      (value "Test Point")
      (footprint "COMATEL_385.0358.1.02.400")
      (description "2 Mini Wire-Wrap Contact Strip Header")
      (fields
        (field (name "PART NUMBER") "COMATEL_385.0358.1.02.400")
        (field (name "MANUFACTURER") "KONTEK COMATEL")
        (field (name "AUTHOR") "CERN DEM JLC")
      )
      (libsource (lib "Connectors") (part "Wire-Wrap Contact x2"))
    )
    (comp (ref "W27")
      (value "Test Point")
      (footprint "COMATEL_385.0358.1.02.400")
      (description "2 Mini Wire-Wrap Contact Strip Header")
      (fields
        (field (name "PART NUMBER") "COMATEL_385.0358.1.02.400")
        (field (name "MANUFACTURER") "KONTEK COMATEL")
        (field (name "AUTHOR") "CERN DEM JLC")
      )
      (libsource (lib "Connectors") (part "Wire-Wrap Contact x2"))
    )
    (comp (ref "W29")
      (value "Test Point")
      (footprint "COMATEL_385.0358.1.02.400")
      (description "2 Mini Wire-Wrap Contact Strip Header")
      (fields
        (field (name "PART NUMBER") "COMATEL_385.0358.1.02.400")
        (field (name "MANUFACTURER") "KONTEK COMATEL")
        (field (name "AUTHOR") "CERN DEM JLC")
      )
      (libsource (lib "Connectors") (part "Wire-Wrap Contact x2"))
    )
    (comp (ref "W31")
      (value "Test Point")
      (footprint "COMATEL_385.0358.1.02.400")
      (description "2 Mini Wire-Wrap Contact Strip Header")
      (fields
        (field (name "PART NUMBER") "COMATEL_385.0358.1.02.400")
        (field (name "MANUFACTURER") "KONTEK COMATEL")
        (field (name "AUTHOR") "CERN DEM JLC")
      )
      (libsource (lib "Connectors") (part "Wire-Wrap Contact x2"))
    )
  )
  (nets
    (net (code "17") (name "/DIR_CTRL1") (class "Default")
      (node (ref "IC3") (pin "4") (pinfunction "P0_4") (pintype "bidirectional"))
      (node (ref "R4") (pin "2") (pinfunction "2_2") (pintype "passive"))
      (node (ref "R5") (pin "1") (pinfunction "1_1") (pintype "passive"))
      (node (ref "SW1") (pin "1") (pinfunction "1_1") (pintype "bidirectional"))
      (node (ref "W1") (pin "1") (pinfunction "1_1") (pintype "bidirectional"))
    )
    (net (code "18") (name "/DIR_CTRL2") (class "Default")
      (node (ref "IC3") (pin "5") (pinfunction "P1_5") (pintype "bidirectional"))
      (node (ref "R6") (pin "2") (pinfunction "2_2") (pintype "passive"))
      (node (ref "R7") (pin "1") (pinfunction "1_1") (pintype "passive"))
      (node (ref "SW2") (pin "1") (pinfunction "1_1") (pintype "bidirectional"))
      (node (ref "W3") (pin "1") (pinfunction "1_1") (pintype "bidirectional"))
    )
    (net (code "19") (name "/DIR_CTRL3") (class "Default")
      (node (ref "IC3") (pin "6") (pinfunction "P2_6") (pintype "bidirectional"))
      (node (ref "R8") (pin "2") (pinfunction "2_2") (pintype "passive"))
      (node (ref "R9") (pin "1") (pinfunction "1_1") (pintype "passive"))
      (node (ref "SW3") (pin "1") (pinfunction "1_1") (pintype "bidirectional"))
      (node (ref "W5") (pin "1") (pinfunction "1_1") (pintype "bidirectional"))
    )
    (net (code "20") (name "/DIR_CTRL4") (class "Default")
      (node (ref "IC3") (pin "7") (pinfunction "P3_7") (pintype "bidirectional"))
      (node (ref "R10") (pin "2") (pinfunction "2_2") (pintype "passive"))
      (node (ref "R11") (pin "1") (pinfunction "1_1") (pintype "passive"))
      (node (ref "SW4") (pin "1") (pinfunction "1_1") (pintype "bidirectional"))
      (node (ref "W7") (pin "1") (pinfunction "1_1") (pintype "bidirectional"))
    )
    (net (code "21") (name "/DIR_CTRL5") (class "Default")
      (node (ref "IC3") (pin "9") (pinfunction "P4_9") (pintype "bidirectional"))
      (node (ref "R12") (pin "2") (pinfunction "2_2") (pintype "passive"))
      (node (ref "R13") (pin "1") (pinfunction "1_1") (pintype "passive"))
      (node (ref "SW5") (pin "1") (pinfunction "1_1") (pintype "bidirectional"))
      (node (ref "W9") (pin "1") (pinfunction "1_1") (pintype "bidirectional"))
    )
    (net (code "22") (name "/DIR_CTRL6") (class "Default")
      (node (ref "IC3") (pin "10") (pinfunction "P5_10") (pintype "bidirectional"))
      (node (ref "R14") (pin "2") (pinfunction "2_2") (pintype "passive"))
      (node (ref "R15") (pin "1") (pinfunction "1_1") (pintype "passive"))
      (node (ref "SW6") (pin "1") (pinfunction "1_1") (pintype "bidirectional"))
      (node (ref "W11") (pin "1") (pinfunction "1_1") (pintype "bidirectional"))
    )
    (net (code "23") (name "/DIR_CTRL7") (class "Default")
      (node (ref "IC3") (pin "11") (pinfunction "P6_11") (pintype "bidirectional"))
      (node (ref "R16") (pin "2") (pinfunction "2_2") (pintype "passive"))
      (node (ref "R17") (pin "1") (pinfunction "1_1") (pintype "passive"))
      (node (ref "SW7") (pin "1") (pinfunction "1_1") (pintype "bidirectional"))
      (node (ref "W13") (pin "1") (pinfunction "1_1") (pintype "bidirectional"))
    )
    (net (code "24") (name "/DIR_CTRL8") (class "Default")
      (node (ref "IC3") (pin "12") (pinfunction "P7_12") (pintype "bidirectional"))
      (node (ref "R18") (pin "2") (pinfunction "2_2") (pintype "passive"))
      (node (ref "R19") (pin "1") (pinfunction "1_1") (pintype "passive"))
      (node (ref "SW8") (pin "1") (pinfunction "1_1") (pintype "bidirectional"))
      (node (ref "W15") (pin "1") (pinfunction "1_1") (pintype "bidirectional"))
    )
    (net (code "25") (name "/DIR_CTRL9") (class "Default")
      (node (ref "IC5") (pin "4") (pinfunction "P0_4") (pintype "bidirectional"))
      (node (ref "R20") (pin "2") (pinfunction "2_2") (pintype "passive"))
      (node (ref "R21") (pin "1") (pinfunction "1_1") (pintype "passive"))
      (node (ref "SW9") (pin "1") (pinfunction "1_1") (pintype "bidirectional"))
      (node (ref "W17") (pin "1") (pinfunction "1_1") (pintype "bidirectional"))
    )
    (net (code "26") (name "/DIR_CTRL10") (class "Default")
      (node (ref "IC5") (pin "5") (pinfunction "P1_5") (pintype "bidirectional"))
      (node (ref "R22") (pin "2") (pinfunction "2_2") (pintype "passive"))
      (node (ref "R23") (pin "1") (pinfunction "1_1") (pintype "passive"))
      (node (ref "SW10") (pin "1") (pinfunction "1_1") (pintype "bidirectional"))
      (node (ref "W19") (pin "1") (pinfunction "1_1") (pintype "bidirectional"))
    )
    (net (code "27") (name "/DIR_CTRL11") (class "Default")
      (node (ref "IC5") (pin "6") (pinfunction "P2_6") (pintype "bidirectional"))
      (node (ref "R24") (pin "2") (pinfunction "2_2") (pintype "passive"))
      (node (ref "R25") (pin "1") (pinfunction "1_1") (pintype "passive"))
      (node (ref "SW11") (pin "1") (pinfunction "1_1") (pintype "bidirectional"))
      (node (ref "W21") (pin "1") (pinfunction "1_1") (pintype "bidirectional"))
    )
    (net (code "28") (name "/DIR_CTRL12") (class "Default")
      (node (ref "IC5") (pin "7") (pinfunction "P3_7") (pintype "bidirectional"))
      (node (ref "R26") (pin "2") (pinfunction "2_2") (pintype "passive"))
      (node (ref "R27") (pin "1") (pinfunction "1_1") (pintype "passive"))
      (node (ref "SW12") (pin "1") (pinfunction "1_1") (pintype "bidirectional"))
      (node (ref "W23") (pin "1") (pinfunction "1_1") (pintype "bidirectional"))
    )
    (net (code "29") (name "/DIR_CTRL13") (class "Default")
      (node (ref "IC5") (pin "9") (pinfunction "P4_9") (pintype "bidirectional"))
      (node (ref "R28") (pin "2") (pinfunction "2_2") (pintype "passive"))
      (node (ref "R29") (pin "1") (pinfunction "1_1") (pintype "passive"))
      (node (ref "SW13") (pin "1") (pinfunction "1_1") (pintype "bidirectional"))
      (node (ref "W25") (pin "1") (pinfunction "1_1") (pintype "bidirectional"))
    )
    (net (code "30") (name "/DIR_CTRL14") (class "Default")
      (node (ref "IC5") (pin "10") (pinfunction "P5_10") (pintype "bidirectional"))
      (node (ref "R30") (pin "2") (pinfunction "2_2") (pintype "passive"))
      (node (ref "R31") (pin "1") (pinfunction "1_1") (pintype "passive"))
      (node (ref "SW14") (pin "1") (pinfunction "1_1") (pintype "bidirectional"))
      (node (ref "W27") (pin "1") (pinfunction "1_1") (pintype "bidirectional"))
    )
    (net (code "31") (name "/DIR_CTRL15") (class "Default")
      (node (ref "IC5") (pin "11") (pinfunction "P6_11") (pintype "bidirectional"))
      (node (ref "R32") (pin "2") (pinfunction "2_2") (pintype "passive"))
      (node (ref "R33") (pin "1") (pinfunction "1_1") (pintype "passive"))
      (node (ref "SW15") (pin "1") (pinfunction "1_1") (pintype "bidirectional"))
      (node (ref "W29") (pin "1") (pinfunction "1_1") (pintype "bidirectional"))
    )
    (net (code "32") (name "/DIR_CTRL16") (class "Default")
      (node (ref "IC5") (pin "12") (pinfunction "P7_12") (pintype "bidirectional"))
      (node (ref "R34") (pin "2") (pinfunction "2_2") (pintype "passive"))
      (node (ref "R35") (pin "1") (pinfunction "1_1") (pintype "passive"))
      (node (ref "SW16") (pin "1") (pinfunction "1_1") (pintype "bidirectional"))
      (node (ref "W31") (pin "1") (pinfunction "1_1") (pintype "bidirectional"))
    )
    (net (code "33") (name "/I2C1_SCL") (class "Default")
      (node (ref "IC3") (pin "14") (pinfunction "SCL_14") (pintype "input"))
      (node (ref "IC4") (pin "1") (pinfunction "SCL_1") (pintype "input"))
      (node (ref "J1") (pin "27") (pinfunction "27_27") (pintype "bidirectional"))
    )
    (net (code "34") (name "/I2C1_SDA") (class "Default")
      (node (ref "IC3") (pin "15") (pinfunction "SDA_15") (pintype "bidirectional"))
      (node (ref "IC4") (pin "3") (pinfunction "SDA_3") (pintype "bidirectional"))
      (node (ref "J1") (pin "26") (pinfunction "26_26") (pintype "bidirectional"))
    )
    (net (code "35") (name "/I2C2_SCL") (class "Default")
      (node (ref "IC5") (pin "14") (pinfunction "SCL_14") (pintype "input"))
      (node (ref "IC6") (pin "1") (pinfunction "SCL_1") (pintype "input"))
      (node (ref "J3") (pin "27") (pinfunction "27_27") (pintype "bidirectional"))
    )
    (net (code "36") (name "/I2C2_SDA") (class "Default")
      (node (ref "IC5") (pin "15") (pinfunction "SDA_15") (pintype "bidirectional"))
      (node (ref "IC6") (pin "3") (pinfunction "SDA_3") (pintype "bidirectional"))
      (node (ref "J3") (pin "26") (pinfunction "26_26") (pintype "bidirectional"))
    )
    (net (code "37") (name "/LVDS1_N") (class "Default")
      (node (ref "J1") (pin "3") (pinfunction "3_3") (pintype "bidirectional"))
    )
    (net (code "38") (name "/LVDS1_P") (class "Default")
      (node (ref "J1") (pin "2") (pinfunction "2_2") (pintype "bidirectional"))
    )
    (net (code "39") (name "/LVDS2_N") (class "Default")
      (node (ref "J1") (pin "6") (pinfunction "6_6") (pintype "bidirectional"))
    )
    (net (code "40") (name "/LVDS2_P") (class "Default")
      (node (ref "J1") (pin "5") (pinfunction "5_5") (pintype "bidirectional"))
    )
    (net (code "41") (name "/LVDS3_N") (class "Default")
      (node (ref "J1") (pin "9") (pinfunction "9_9") (pintype "bidirectional"))
    )
    (net (code "42") (name "/LVDS3_P") (class "Default")
      (node (ref "J1") (pin "8") (pinfunction "8_8") (pintype "bidirectional"))
    )
    (net (code "43") (name "/LVDS4_N") (class "Default")
      (node (ref "J1") (pin "12") (pinfunction "12_12") (pintype "bidirectional"))
    )
    (net (code "44") (name "/LVDS4_P") (class "Default")
      (node (ref "J1") (pin "11") (pinfunction "11_11") (pintype "bidirectional"))
    )
    (net (code "45") (name "/LVDS5_N") (class "Default")
      (node (ref "J1") (pin "15") (pinfunction "15_15") (pintype "bidirectional"))
    )
    (net (code "46") (name "/LVDS5_P") (class "Default")
      (node (ref "J1") (pin "14") (pinfunction "14_14") (pintype "bidirectional"))
    )
    (net (code "47") (name "/LVDS6_N") (class "Default")
      (node (ref "J1") (pin "18") (pinfunction "18_18") (pintype "bidirectional"))
    )
    (net (code "48") (name "/LVDS6_P") (class "Default")
      (node (ref "J1") (pin "17") (pinfunction "17_17") (pintype "bidirectional"))
    )
    (net (code "49") (name "/LVDS7_N") (class "Default")
      (node (ref "J1") (pin "21") (pinfunction "21_21") (pintype "bidirectional"))
    )
    (net (code "50") (name "/LVDS7_P") (class "Default")
      (node (ref "J1") (pin "20") (pinfunction "20_20") (pintype "bidirectional"))
    )
    (net (code "51") (name "/LVDS8_N") (class "Default")
      (node (ref "J1") (pin "24") (pinfunction "24_24") (pintype "bidirectional"))
    )
    (net (code "52") (name "/LVDS8_P") (class "Default")
      (node (ref "J1") (pin "23") (pinfunction "23_23") (pintype "bidirectional"))
    )
    (net (code "53") (name "/LVDS9_N") (class "Default")
      (node (ref "J3") (pin "3") (pinfunction "3_3") (pintype "bidirectional"))
    )
    (net (code "54") (name "/LVDS9_P") (class "Default")
      (node (ref "J3") (pin "2") (pinfunction "2_2") (pintype "bidirectional"))
    )
    (net (code "55") (name "/LVDS10_N") (class "Default")
      (node (ref "J3") (pin "6") (pinfunction "6_6") (pintype "bidirectional"))
    )
    (net (code "56") (name "/LVDS10_P") (class "Default")
      (node (ref "J3") (pin "5") (pinfunction "5_5") (pintype "bidirectional"))
    )
    (net (code "57") (name "/LVDS11_N") (class "Default")
      (node (ref "J3") (pin "9") (pinfunction "9_9") (pintype "bidirectional"))
    )
    (net (code "58") (name "/LVDS11_P") (class "Default")
      (node (ref "J3") (pin "8") (pinfunction "8_8") (pintype "bidirectional"))
    )
    (net (code "59") (name "/LVDS12_N") (class "Default")
      (node (ref "J3") (pin "12") (pinfunction "12_12") (pintype "bidirectional"))
    )
    (net (code "60") (name "/LVDS12_P") (class "Default")
      (node (ref "J3") (pin "11") (pinfunction "11_11") (pintype "bidirectional"))
    )
    (net (code "61") (name "/LVDS13_N") (class "Default")
      (node (ref "J3") (pin "15") (pinfunction "15_15") (pintype "bidirectional"))
    )
    (net (code "62") (name "/LVDS13_P") (class "Default")
      (node (ref "J3") (pin "14") (pinfunction "14_14") (pintype "bidirectional"))
    )
    (net (code "63") (name "/LVDS14_N") (class "Default")
      (node (ref "J3") (pin "18") (pinfunction "18_18") (pintype "bidirectional"))
    )
    (net (code "64") (name "/LVDS14_P") (class "Default")
      (node (ref "J3") (pin "17") (pinfunction "17_17") (pintype "bidirectional"))
    )
    (net (code "65") (name "/LVDS15_N") (class "Default")
      (node (ref "J3") (pin "21") (pinfunction "21_21") (pintype "bidirectional"))
    )
    (net (code "66") (name "/LVDS15_P") (class "Default")
      (node (ref "J3") (pin "20") (pinfunction "20_20") (pintype "bidirectional"))
    )
    (net (code "67") (name "/LVDS16_N") (class "Default")
      (node (ref "J3") (pin "24") (pinfunction "24_24") (pintype "bidirectional"))
    )
    (net (code "68") (name "/LVDS16_P") (class "Default")
      (node (ref "J3") (pin "23") (pinfunction "23_23") (pintype "bidirectional"))
    )
    (net (code "69") (name "/LVDS_IOA_N") (class "Default")
      (node (ref "J2") (pin "8A") (pinfunction "8_8A") (pintype "bidirectional"))
    )
    (net (code "70") (name "/LVDS_IOA_N_1") (class "Default")
      (node (ref "J2") (pin "2B") (pinfunction "2_2B") (pintype "bidirectional"))
    )
    (net (code "71") (name "/LVDS_IOA_N_2") (class "Default")
      (node (ref "J2") (pin "4B") (pinfunction "4_4B") (pintype "bidirectional"))
    )
    (net (code "72") (name "/LVDS_IOA_N_3") (class "Default")
      (node (ref "J2") (pin "6B") (pinfunction "6_6B") (pintype "bidirectional"))
    )
    (net (code "73") (name "/LVDS_IOA_N_4") (class "Default")
      (node (ref "J2") (pin "8B") (pinfunction "8_8B") (pintype "bidirectional"))
    )
    (net (code "74") (name "/LVDS_IOA_N_5") (class "Default")
      (node (ref "J2") (pin "2C") (pinfunction "2_2C") (pintype "bidirectional"))
    )
    (net (code "75") (name "/LVDS_IOA_N_6") (class "Default")
      (node (ref "J2") (pin "4C") (pinfunction "4_4C") (pintype "bidirectional"))
    )
    (net (code "76") (name "/LVDS_IOA_N_7") (class "Default")
      (node (ref "J2") (pin "6C") (pinfunction "6_6C") (pintype "bidirectional"))
    )
    (net (code "77") (name "/LVDS_IOA_N_8") (class "Default")
      (node (ref "J2") (pin "8C") (pinfunction "8_8C") (pintype "bidirectional"))
    )
    (net (code "78") (name "/LVDS_IOA_N_9") (class "Default")
      (node (ref "J2") (pin "2D") (pinfunction "2_2D") (pintype "bidirectional"))
    )
    (net (code "79") (name "/LVDS_IOA_N_10") (class "Default")
      (node (ref "J2") (pin "4D") (pinfunction "4_4D") (pintype "bidirectional"))
    )
    (net (code "80") (name "/LVDS_IOA_N_11") (class "Default")
      (node (ref "J2") (pin "6D") (pinfunction "6_6D") (pintype "bidirectional"))
    )
    (net (code "81") (name "/LVDS_IOA_N_12") (class "Default")
      (node (ref "J2") (pin "8D") (pinfunction "8_8D") (pintype "bidirectional"))
    )
    (net (code "82") (name "/LVDS_IOA_N_13") (class "Default")
      (node (ref "J2") (pin "2A") (pinfunction "2_2A") (pintype "bidirectional"))
    )
    (net (code "83") (name "/LVDS_IOA_N_14") (class "Default")
      (node (ref "J2") (pin "4A") (pinfunction "4_4A") (pintype "bidirectional"))
    )
    (net (code "84") (name "/LVDS_IOA_N_15") (class "Default")
      (node (ref "J2") (pin "6A") (pinfunction "6_6A") (pintype "bidirectional"))
    )
    (net (code "85") (name "/LVDS_IOA_P") (class "Default")
      (node (ref "J2") (pin "1B") (pinfunction "1_1B") (pintype "bidirectional"))
    )
    (net (code "86") (name "/LVDS_IOA_P_1") (class "Default")
      (node (ref "J2") (pin "3B") (pinfunction "3_3B") (pintype "bidirectional"))
    )
    (net (code "87") (name "/LVDS_IOA_P_2") (class "Default")
      (node (ref "J2") (pin "5B") (pinfunction "5_5B") (pintype "bidirectional"))
    )
    (net (code "88") (name "/LVDS_IOA_P_3") (class "Default")
      (node (ref "J2") (pin "7B") (pinfunction "7_7B") (pintype "bidirectional"))
    )
    (net (code "89") (name "/LVDS_IOA_P_4") (class "Default")
      (node (ref "J2") (pin "1C") (pinfunction "1_1C") (pintype "bidirectional"))
    )
    (net (code "90") (name "/LVDS_IOA_P_5") (class "Default")
      (node (ref "J2") (pin "5C") (pinfunction "5_5C") (pintype "bidirectional"))
    )
    (net (code "91") (name "/LVDS_IOA_P_6") (class "Default")
      (node (ref "J2") (pin "3C") (pinfunction "3_3C") (pintype "bidirectional"))
    )
    (net (code "92") (name "/LVDS_IOA_P_7") (class "Default")
      (node (ref "J2") (pin "7C") (pinfunction "7_7C") (pintype "bidirectional"))
    )
    (net (code "93") (name "/LVDS_IOA_P_8") (class "Default")
      (node (ref "J2") (pin "1D") (pinfunction "1_1D") (pintype "bidirectional"))
    )
    (net (code "94") (name "/LVDS_IOA_P_9") (class "Default")
      (node (ref "J2") (pin "5D") (pinfunction "5_5D") (pintype "bidirectional"))
    )
    (net (code "95") (name "/LVDS_IOA_P_10") (class "Default")
      (node (ref "J2") (pin "7D") (pinfunction "7_7D") (pintype "bidirectional"))
    )
    (net (code "96") (name "/LVDS_IOA_P_11") (class "Default")
      (node (ref "J2") (pin "3D") (pinfunction "3_3D") (pintype "bidirectional"))
    )
    (net (code "97") (name "/LVDS_IOA_P_12") (class "Default")
      (node (ref "J2") (pin "1A") (pinfunction "1_1A") (pintype "bidirectional"))
    )
    (net (code "98") (name "/LVDS_IOA_P_13") (class "Default")
      (node (ref "J2") (pin "3A") (pinfunction "3_3A") (pintype "bidirectional"))
    )
    (net (code "99") (name "/LVDS_IOA_P_14") (class "Default")
      (node (ref "J2") (pin "5A") (pinfunction "5_5A") (pintype "bidirectional"))
    )
    (net (code "100") (name "/LVDS_IOA_P_15") (class "Default")
      (node (ref "J2") (pin "7A") (pinfunction "7_7A") (pintype "bidirectional"))
    )
    (net (code "101") (name "GND") (class "Default")
      (node (ref "C10") (pin "1") (pinfunction "1_1") (pintype "passive"))
      (node (ref "C11") (pin "1") (pinfunction "1_1") (pintype "passive"))
      (node (ref "C12") (pin "1") (pinfunction "1_1") (pintype "passive"))
      (node (ref "C13") (pin "1") (pinfunction "1_1") (pintype "passive"))
      (node (ref "C14") (pin "1") (pinfunction "1_1") (pintype "passive"))
      (node (ref "C3") (pin "1") (pinfunction "1_1") (pintype "passive"))
      (node (ref "C4") (pin "1") (pinfunction "1_1") (pintype "passive"))
      (node (ref "C5") (pin "1") (pinfunction "1_1") (pintype "passive"))
      (node (ref "C6") (pin "1") (pinfunction "1_1") (pintype "passive"))
      (node (ref "C7") (pin "1") (pinfunction "1_1") (pintype "passive"))
      (node (ref "C8") (pin "2") (pinfunction "2_2") (pintype "passive"))
      (node (ref "C9") (pin "1") (pinfunction "1_1") (pintype "passive"))
      (node (ref "IC3") (pin "1") (pinfunction "A0_1") (pintype "input"))
      (node (ref "IC3") (pin "8") (pinfunction "GND_8") (pintype "power_in"))
      (node (ref "IC4") (pin "2") (pinfunction "VSS_2") (pintype "power_in"))
      (node (ref "IC5") (pin "1") (pinfunction "A0_1") (pintype "input"))
      (node (ref "IC5") (pin "8") (pinfunction "GND_8") (pintype "power_in"))
      (node (ref "IC6") (pin "2") (pinfunction "VSS_2") (pintype "power_in"))
      (node (ref "IC7") (pin "1") (pinfunction "PGND_1") (pintype "power_in"))
      (node (ref "IC7") (pin "11") (pinfunction "EP_11") (pintype "power_in"))
      (node (ref "IC7") (pin "6") (pinfunction "AGND_6") (pintype "power_in"))
      (node (ref "J1") (pin "1") (pinfunction "1_1") (pintype "bidirectional"))
      (node (ref "J1") (pin "10") (pinfunction "10_10") (pintype "bidirectional"))
      (node (ref "J1") (pin "13") (pinfunction "13_13") (pintype "bidirectional"))
      (node (ref "J1") (pin "16") (pinfunction "16_16") (pintype "bidirectional"))
      (node (ref "J1") (pin "19") (pinfunction "19_19") (pintype "bidirectional"))
      (node (ref "J1") (pin "22") (pinfunction "22_22") (pintype "bidirectional"))
      (node (ref "J1") (pin "25") (pinfunction "25_25") (pintype "bidirectional"))
      (node (ref "J1") (pin "4") (pinfunction "4_4") (pintype "bidirectional"))
      (node (ref "J1") (pin "7") (pinfunction "7_7") (pintype "bidirectional"))
      (node (ref "J2") (pin "SH") (pinfunction "1_SH") (pintype "passive"))
      (node (ref "J3") (pin "1") (pinfunction "1_1") (pintype "bidirectional"))
      (node (ref "J3") (pin "10") (pinfunction "10_10") (pintype "bidirectional"))
      (node (ref "J3") (pin "13") (pinfunction "13_13") (pintype "bidirectional"))
      (node (ref "J3") (pin "16") (pinfunction "16_16") (pintype "bidirectional"))
      (node (ref "J3") (pin "19") (pinfunction "19_19") (pintype "bidirectional"))
      (node (ref "J3") (pin "22") (pinfunction "22_22") (pintype "bidirectional"))
      (node (ref "J3") (pin "25") (pinfunction "25_25") (pintype "bidirectional"))
      (node (ref "J3") (pin "4") (pinfunction "4_4") (pintype "bidirectional"))
      (node (ref "J3") (pin "7") (pinfunction "7_7") (pintype "bidirectional"))
      (node (ref "R37") (pin "1") (pinfunction "1_1") (pintype "passive"))
      (node (ref "W1") (pin "2") (pinfunction "2_2") (pintype "bidirectional"))
      (node (ref "W11") (pin "2") (pinfunction "2_2") (pintype "bidirectional"))
      (node (ref "W13") (pin "2") (pinfunction "2_2") (pintype "bidirectional"))
      (node (ref "W15") (pin "2") (pinfunction "2_2") (pintype "bidirectional"))
      (node (ref "W17") (pin "2") (pinfunction "2_2") (pintype "bidirectional"))
      (node (ref "W19") (pin "2") (pinfunction "2_2") (pintype "bidirectional"))
      (node (ref "W21") (pin "2") (pinfunction "2_2") (pintype "bidirectional"))
      (node (ref "W23") (pin "2") (pinfunction "2_2") (pintype "bidirectional"))
      (node (ref "W25") (pin "2") (pinfunction "2_2") (pintype "bidirectional"))
      (node (ref "W27") (pin "2") (pinfunction "2_2") (pintype "bidirectional"))
      (node (ref "W29") (pin "2") (pinfunction "2_2") (pintype "bidirectional"))
      (node (ref "W3") (pin "2") (pinfunction "2_2") (pintype "bidirectional"))
      (node (ref "W31") (pin "2") (pinfunction "2_2") (pintype "bidirectional"))
      (node (ref "W5") (pin "2") (pinfunction "2_2") (pintype "bidirectional"))
      (node (ref "W7") (pin "2") (pinfunction "2_2") (pintype "bidirectional"))
      (node (ref "W9") (pin "2") (pinfunction "2_2") (pintype "bidirectional"))
    )
    (net (code "102") (name "Net-(IC7-FB)") (class "Default")
      (node (ref "IC7") (pin "5") (pinfunction "FB_5") (pintype "input"))
      (node (ref "R36") (pin "1") (pinfunction "1_1") (pintype "passive"))
      (node (ref "R37") (pin "2") (pinfunction "2_2") (pintype "passive"))
    )
    (net (code "103") (name "Net-(IC7-SW)") (class "Default")
      (node (ref "IC7") (pin "9") (pinfunction "SW_9") (pintype "output"))
      (node (ref "L1") (pin "1") (pinfunction "1_1") (pintype "passive"))
    )
    (net (code "104") (name "Net-(LD1-C)") (class "Default")
      (node (ref "LD1") (pin "1") (pinfunction "C_1") (pintype "passive"))
      (node (ref "R4") (pin "1") (pinfunction "1_1") (pintype "passive"))
    )
    (net (code "105") (name "Net-(LD2-C)") (class "Default")
      (node (ref "LD2") (pin "1") (pinfunction "C_1") (pintype "passive"))
      (node (ref "R6") (pin "1") (pinfunction "1_1") (pintype "passive"))
    )
    (net (code "106") (name "Net-(LD3-C)") (class "Default")
      (node (ref "LD3") (pin "1") (pinfunction "C_1") (pintype "passive"))
      (node (ref "R8") (pin "1") (pinfunction "1_1") (pintype "passive"))
    )
    (net (code "107") (name "Net-(LD4-C)") (class "Default")
      (node (ref "LD4") (pin "1") (pinfunction "C_1") (pintype "passive"))
      (node (ref "R10") (pin "1") (pinfunction "1_1") (pintype "passive"))
    )
    (net (code "108") (name "Net-(LD5-C)") (class "Default")
      (node (ref "LD5") (pin "1") (pinfunction "C_1") (pintype "passive"))
      (node (ref "R12") (pin "1") (pinfunction "1_1") (pintype "passive"))
    )
    (net (code "109") (name "Net-(LD6-C)") (class "Default")
      (node (ref "LD6") (pin "1") (pinfunction "C_1") (pintype "passive"))
      (node (ref "R14") (pin "1") (pinfunction "1_1") (pintype "passive"))
    )
    (net (code "110") (name "Net-(LD7-C)") (class "Default")
      (node (ref "LD7") (pin "1") (pinfunction "C_1") (pintype "passive"))
      (node (ref "R16") (pin "1") (pinfunction "1_1") (pintype "passive"))
    )
    (net (code "111") (name "Net-(LD8-C)") (class "Default")
      (node (ref "LD8") (pin "1") (pinfunction "C_1") (pintype "passive"))
      (node (ref "R18") (pin "1") (pinfunction "1_1") (pintype "passive"))
    )
    (net (code "112") (name "Net-(LD9-C)") (class "Default")
      (node (ref "LD9") (pin "1") (pinfunction "C_1") (pintype "passive"))
      (node (ref "R20") (pin "1") (pinfunction "1_1") (pintype "passive"))
    )
    (net (code "113") (name "Net-(LD10-C)") (class "Default")
      (node (ref "LD10") (pin "1") (pinfunction "C_1") (pintype "passive"))
      (node (ref "R22") (pin "1") (pinfunction "1_1") (pintype "passive"))
    )
    (net (code "114") (name "Net-(LD11-C)") (class "Default")
      (node (ref "LD11") (pin "1") (pinfunction "C_1") (pintype "passive"))
      (node (ref "R24") (pin "1") (pinfunction "1_1") (pintype "passive"))
    )
    (net (code "115") (name "Net-(LD12-C)") (class "Default")
      (node (ref "LD12") (pin "1") (pinfunction "C_1") (pintype "passive"))
      (node (ref "R26") (pin "1") (pinfunction "1_1") (pintype "passive"))
    )
    (net (code "116") (name "Net-(LD13-C)") (class "Default")
      (node (ref "LD13") (pin "1") (pinfunction "C_1") (pintype "passive"))
      (node (ref "R28") (pin "1") (pinfunction "1_1") (pintype "passive"))
    )
    (net (code "117") (name "Net-(LD14-C)") (class "Default")
      (node (ref "LD14") (pin "1") (pinfunction "C_1") (pintype "passive"))
      (node (ref "R30") (pin "1") (pinfunction "1_1") (pintype "passive"))
    )
    (net (code "118") (name "Net-(LD15-C)") (class "Default")
      (node (ref "LD15") (pin "1") (pinfunction "C_1") (pintype "passive"))
      (node (ref "R32") (pin "1") (pinfunction "1_1") (pintype "passive"))
    )
    (net (code "119") (name "Net-(LD16-C)") (class "Default")
      (node (ref "LD16") (pin "1") (pinfunction "C_1") (pintype "passive"))
      (node (ref "R34") (pin "1") (pinfunction "1_1") (pintype "passive"))
    )
    (net (code "120") (name "P3V3") (class "Default")
      (node (ref "C11") (pin "2") (pinfunction "2_2") (pintype "passive"))
      (node (ref "C12") (pin "2") (pinfunction "2_2") (pintype "passive"))
      (node (ref "C5") (pin "2") (pinfunction "2_2") (pintype "passive"))
      (node (ref "C6") (pin "2") (pinfunction "2_2") (pintype "passive"))
      (node (ref "C7") (pin "2") (pinfunction "2_2") (pintype "passive"))
      (node (ref "C8") (pin "1") (pinfunction "1_1") (pintype "passive"))
      (node (ref "IC7") (pin "10") (pinfunction "VOS_10") (pintype "input"))
      (node (ref "IC7") (pin "8") (pinfunction "SLEEP_8") (pintype "input"))
      (node (ref "L1") (pin "2") (pinfunction "2_2") (pintype "passive"))
      (node (ref "LD1") (pin "2") (pinfunction "A_2") (pintype "passive"))
      (node (ref "LD10") (pin "2") (pinfunction "A_2") (pintype "passive"))
      (node (ref "LD11") (pin "2") (pinfunction "A_2") (pintype "passive"))
      (node (ref "LD12") (pin "2") (pinfunction "A_2") (pintype "passive"))
      (node (ref "LD13") (pin "2") (pinfunction "A_2") (pintype "passive"))
      (node (ref "LD14") (pin "2") (pinfunction "A_2") (pintype "passive"))
      (node (ref "LD15") (pin "2") (pinfunction "A_2") (pintype "passive"))
      (node (ref "LD16") (pin "2") (pinfunction "A_2") (pintype "passive"))
      (node (ref "LD2") (pin "2") (pinfunction "A_2") (pintype "passive"))
      (node (ref "LD3") (pin "2") (pinfunction "A_2") (pintype "passive"))
      (node (ref "LD4") (pin "2") (pinfunction "A_2") (pintype "passive"))
      (node (ref "LD5") (pin "2") (pinfunction "A_2") (pintype "passive"))
      (node (ref "LD6") (pin "2") (pinfunction "A_2") (pintype "passive"))
      (node (ref "LD7") (pin "2") (pinfunction "A_2") (pintype "passive"))
      (node (ref "LD8") (pin "2") (pinfunction "A_2") (pintype "passive"))
      (node (ref "LD9") (pin "2") (pinfunction "A_2") (pintype "passive"))
      (node (ref "R11") (pin "2") (pinfunction "2_2") (pintype "passive"))
      (node (ref "R13") (pin "2") (pinfunction "2_2") (pintype "passive"))
      (node (ref "R15") (pin "2") (pinfunction "2_2") (pintype "passive"))
      (node (ref "R17") (pin "2") (pinfunction "2_2") (pintype "passive"))
      (node (ref "R19") (pin "2") (pinfunction "2_2") (pintype "passive"))
      (node (ref "R21") (pin "2") (pinfunction "2_2") (pintype "passive"))
      (node (ref "R23") (pin "2") (pinfunction "2_2") (pintype "passive"))
      (node (ref "R25") (pin "2") (pinfunction "2_2") (pintype "passive"))
      (node (ref "R27") (pin "2") (pinfunction "2_2") (pintype "passive"))
      (node (ref "R29") (pin "2") (pinfunction "2_2") (pintype "passive"))
      (node (ref "R31") (pin "2") (pinfunction "2_2") (pintype "passive"))
      (node (ref "R33") (pin "2") (pinfunction "2_2") (pintype "passive"))
      (node (ref "R35") (pin "2") (pinfunction "2_2") (pintype "passive"))
      (node (ref "R36") (pin "2") (pinfunction "2_2") (pintype "passive"))
      (node (ref "R5") (pin "2") (pinfunction "2_2") (pintype "passive"))
      (node (ref "R7") (pin "2") (pinfunction "2_2") (pintype "passive"))
      (node (ref "R9") (pin "2") (pinfunction "2_2") (pintype "passive"))
    )
    (net (code "121") (name "P3V3_MP") (class "Default")
      (node (ref "IC3") (pin "2") (pinfunction "A1_2") (pintype "input"))
      (node (ref "IC3") (pin "3") (pinfunction "A2_3") (pintype "input"))
      (node (ref "IC5") (pin "2") (pinfunction "A1_2") (pintype "input"))
      (node (ref "IC5") (pin "3") (pinfunction "A2_3") (pintype "input"))
    )
    (net (code "122") (name "P3V3_MP1") (class "Default")
      (node (ref "C3") (pin "2") (pinfunction "2_2") (pintype "passive"))
      (node (ref "C4") (pin "2") (pinfunction "2_2") (pintype "passive"))
      (node (ref "IC3") (pin "16") (pinfunction "VCC_16") (pintype "bidirectional"))
      (node (ref "IC4") (pin "4") (pinfunction "VCC_4") (pintype "power_in"))
      (node (ref "J1") (pin "30") (pinfunction "30_30") (pintype "bidirectional"))
    )
    (net (code "123") (name "P3V3_MP2") (class "Default")
      (node (ref "C10") (pin "2") (pinfunction "2_2") (pintype "passive"))
      (node (ref "C9") (pin "2") (pinfunction "2_2") (pintype "passive"))
      (node (ref "IC5") (pin "16") (pinfunction "VCC_16") (pintype "bidirectional"))
      (node (ref "IC6") (pin "4") (pinfunction "VCC_4") (pintype "power_in"))
      (node (ref "J3") (pin "30") (pinfunction "30_30") (pintype "bidirectional"))
    )
    (net (code "124") (name "P12V0") (class "Default")
      (node (ref "C13") (pin "2") (pinfunction "2_2") (pintype "passive"))
      (node (ref "C14") (pin "2") (pinfunction "2_2") (pintype "passive"))
      (node (ref "IC7") (pin "2") (pinfunction "VIN_2") (pintype "input"))
      (node (ref "IC7") (pin "3") (pinfunction "EN_3") (pintype "input"))
      (node (ref "J1") (pin "28") (pinfunction "28_28") (pintype "bidirectional"))
      (node (ref "J1") (pin "29") (pinfunction "29_29") (pintype "bidirectional"))
      (node (ref "J3") (pin "28") (pinfunction "28_28") (pintype "bidirectional"))
      (node (ref "J3") (pin "29") (pinfunction "29_29") (pintype "bidirectional"))
    )
    (net (code "125") (name "unconnected-(IC3-~{INT}-Pad13)") (class "Default")
      (node (ref "IC3") (pin "13") (pinfunction "~{INT}_13") (pintype "output"))
    )
    (net (code "126") (name "unconnected-(IC4-NC-Pad5)") (class "Default")
      (node (ref "IC4") (pin "5") (pinfunction "NC_5") (pintype "passive"))
    )
    (net (code "127") (name "unconnected-(IC5-~{INT}-Pad13)") (class "Default")
      (node (ref "IC5") (pin "13") (pinfunction "~{INT}_13") (pintype "output"))
    )
    (net (code "128") (name "unconnected-(IC6-NC-Pad5)") (class "Default")
      (node (ref "IC6") (pin "5") (pinfunction "NC_5") (pintype "passive"))
    )
    (net (code "129") (name "unconnected-(IC7-NC-Pad4)") (class "Default")
      (node (ref "IC7") (pin "4") (pinfunction "NC_4") (pintype "passive"))
    )
    (net (code "130") (name "unconnected-(IC7-PG-Pad7)") (class "Default")
      (node (ref "IC7") (pin "7") (pinfunction "PG_7") (pintype "output"))
    )
    (net (code "131") (name "unconnected-(J4-Pad1)") (class "Default")
      (node (ref "J4") (pin "1") (pinfunction "1_1") (pintype "bidirectional"))
    )
    (net (code "132") (name "unconnected-(J4-Pad2)") (class "Default")
      (node (ref "J4") (pin "2") (pinfunction "2_2") (pintype "bidirectional"))
    )
    (net (code "133") (name "unconnected-(J4-Pad3)") (class "Default")
      (node (ref "J4") (pin "3") (pinfunction "3_3") (pintype "bidirectional"))
    )
    (net (code "134") (name "unconnected-(J4-Pad4)") (class "Default")
      (node (ref "J4") (pin "4") (pinfunction "4_4") (pintype "bidirectional"))
    )
    (net (code "135") (name "unconnected-(J4-Pad5)") (class "Default")
      (node (ref "J4") (pin "5") (pinfunction "5_5") (pintype "bidirectional"))
    )
    (net (code "136") (name "unconnected-(J4-Pad6)") (class "Default")
      (node (ref "J4") (pin "6") (pinfunction "6_6") (pintype "bidirectional"))
    )
    (net (code "137") (name "unconnected-(J4-Pad7)") (class "Default")
      (node (ref "J4") (pin "7") (pinfunction "7_7") (pintype "bidirectional"))
    )
    (net (code "138") (name "unconnected-(J4-Pad8)") (class "Default")
      (node (ref "J4") (pin "8") (pinfunction "8_8") (pintype "bidirectional"))
    )
    (net (code "139") (name "unconnected-(J4-PadSHIELD)") (class "Default")
      (node (ref "J4") (pin "SHIELD") (pinfunction "SHIELD_SHIELD") (pintype "passive"))
    )
  )
)
